# ESS-BoB.net
KiCad netlist of a schematic drawn in Altium Designer
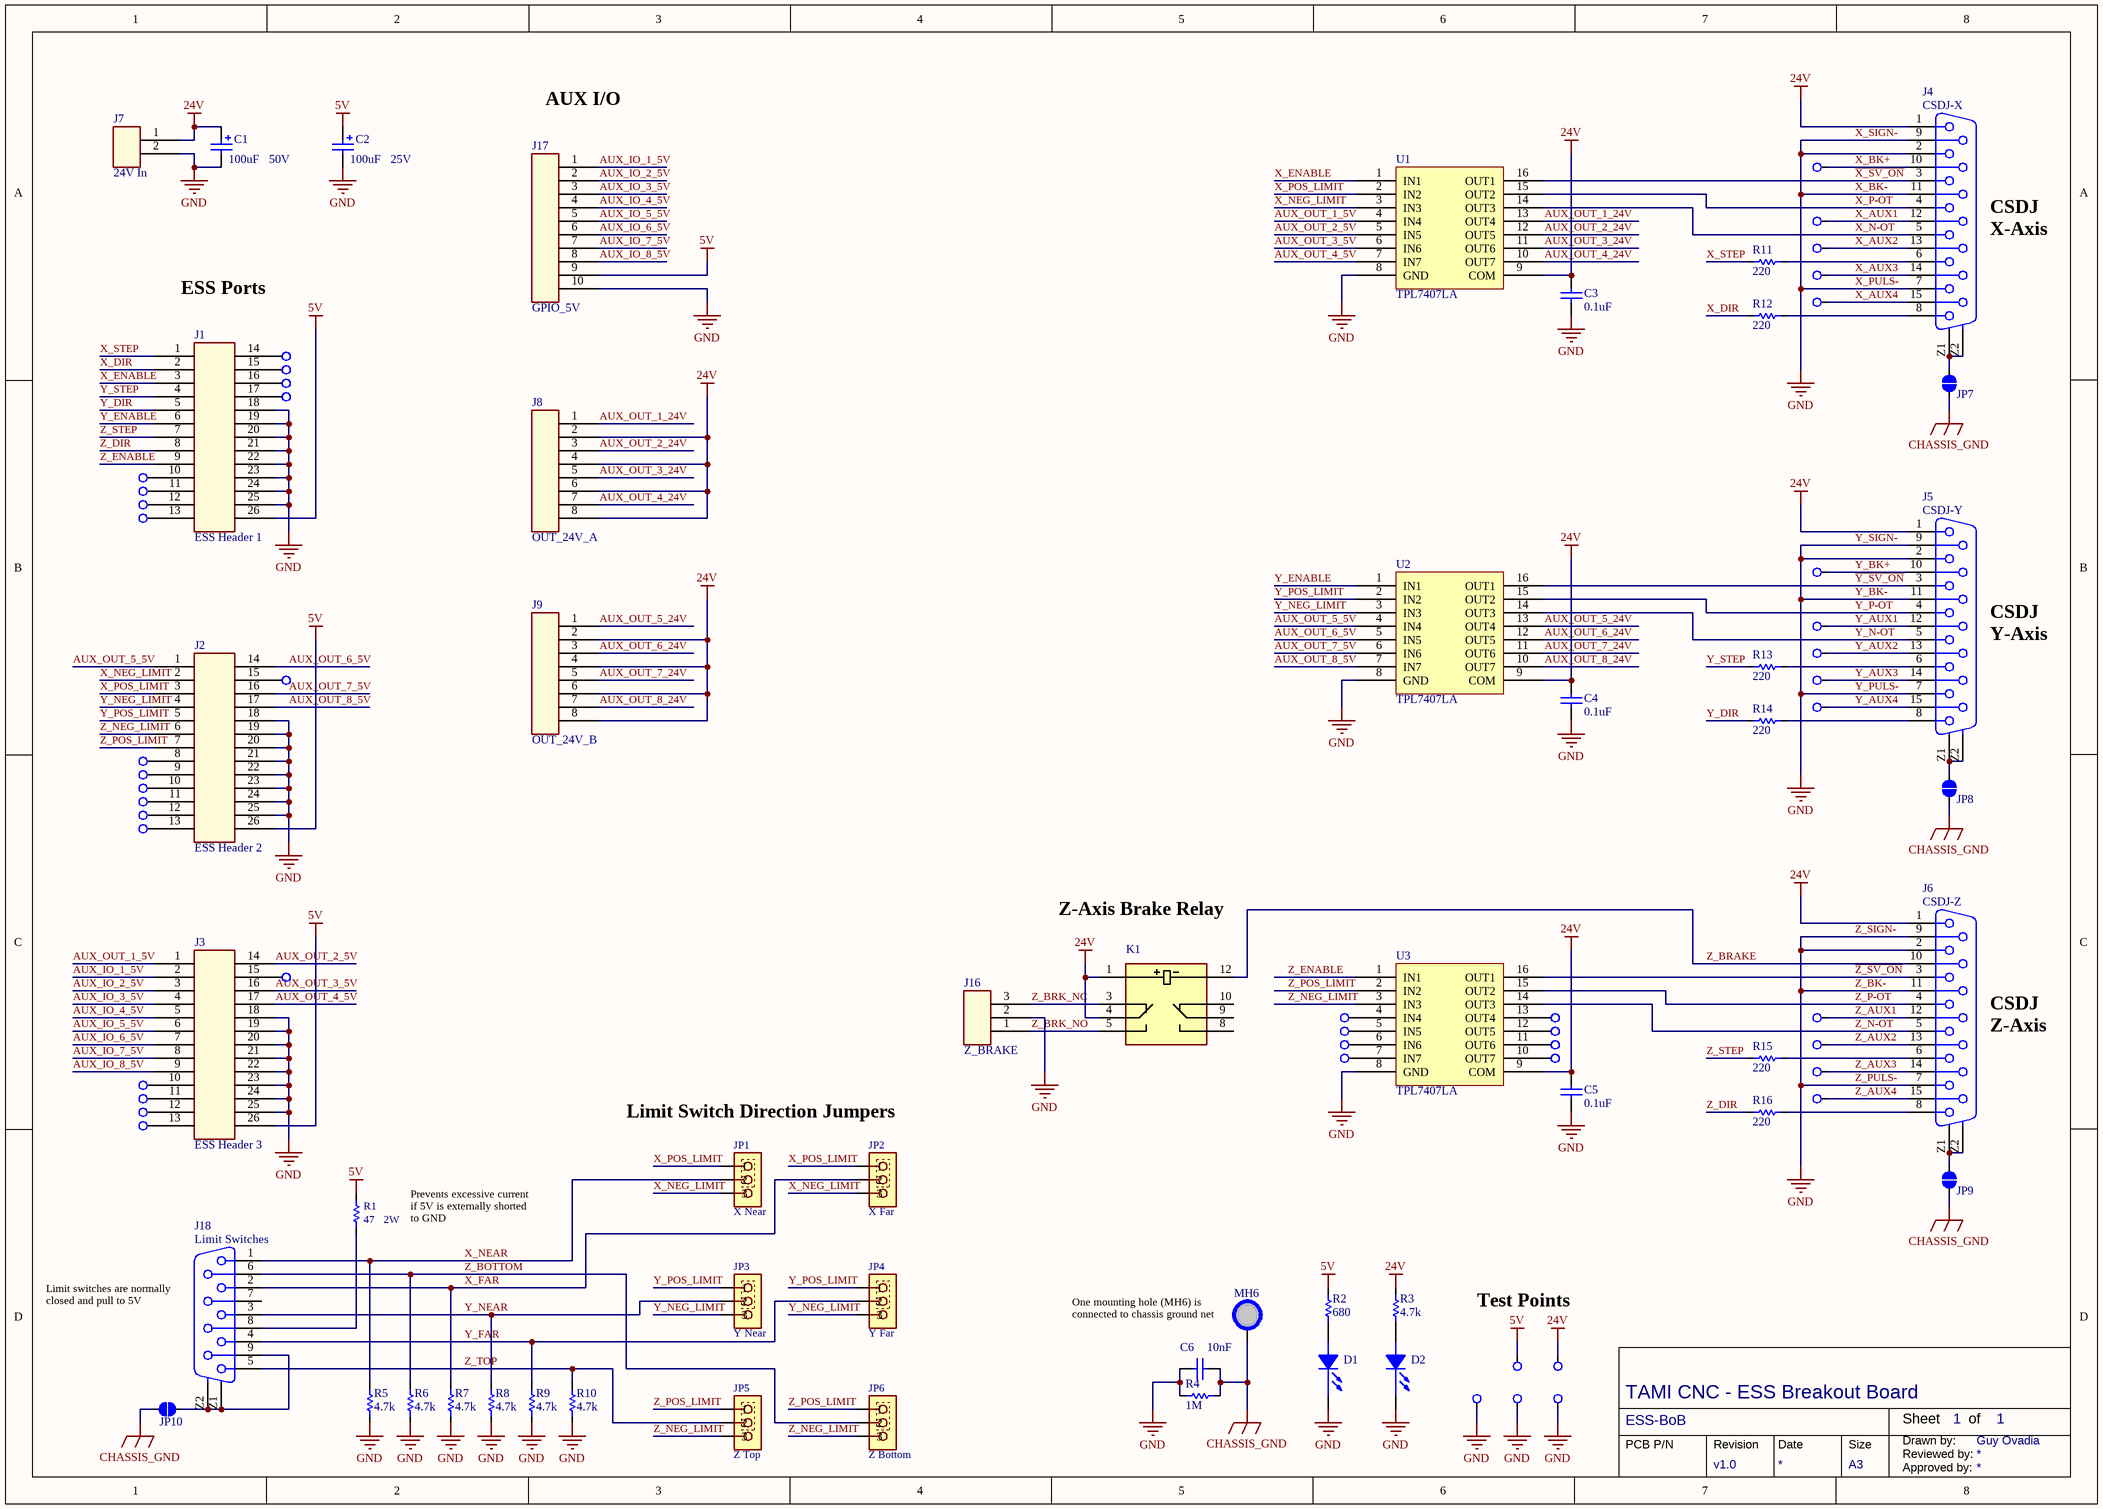
[diagram p0: ESS-BoB.SchDoc]

(export (version "E")
  (design (tool "Eeschema 10.0.6"))
  (components
    (comp (ref "C1")
      (value "100uF")
      (footprint "CAPPR3.5-8x12")
      (description "Polarized Capacitor")
      (fields
        (field (name "TOLERANCE") "TBD %")
        (field (name "VOLTAGE RATING") "50V")
        (field (name "Comment") "Cap Polarized")
      )
      (libsource (lib "my parts library") (part "Cap Polarized"))
    )
    (comp (ref "C2")
      (value "100uF")
      (footprint "CAPPR2-5x11")
      (description "Polarized Capacitor")
      (fields
        (field (name "TOLERANCE") "TBD %")
        (field (name "VOLTAGE RATING") "25V")
        (field (name "Comment") "Cap Polarized")
      )
      (libsource (lib "my parts library") (part "Cap Polarized"))
    )
    (comp (ref "C3")
      (value "0.1uF")
      (footprint "CAPC2012N")
      (description "Capacitor, non-polarized")
      (fields (field (name "TOLERANCE") "TBD %") (field (name "Comment") "Cap non-polarized"))
      (libsource (lib "my parts library") (part "Cap non-polarized"))
    )
    (comp (ref "C4")
      (value "0.1uF")
      (footprint "CAPC2012N")
      (description "Capacitor, non-polarized")
      (fields (field (name "TOLERANCE") "TBD %") (field (name "Comment") "Cap non-polarized"))
      (libsource (lib "my parts library") (part "Cap non-polarized"))
    )
    (comp (ref "C5")
      (value "0.1uF")
      (footprint "CAPC2012N")
      (description "Capacitor, non-polarized")
      (fields (field (name "TOLERANCE") "TBD %") (field (name "Comment") "Cap non-polarized"))
      (libsource (lib "my parts library") (part "Cap non-polarized"))
    )
    (comp (ref "C6")
      (value "10nF")
      (footprint "CAPC2012N")
      (description "Capacitor, non-polarized")
      (fields (field (name "TOLERANCE") "TBD %") (field (name "Comment") "Cap non-polarized"))
      (libsource (lib "my parts library") (part "Cap non-polarized"))
    )
    (comp (ref "D1") (value "5V") (footprint "LED-3MM-RED") (libsource (lib "my parts library") (part "LED")))
    (comp (ref "D2")
      (value "24V")
      (footprint "LED-3MM-RED")
      (libsource (lib "my parts library") (part "LED"))
    )
    (comp (ref "J1")
      (value "ESS Header 1")
      (footprint "Samtec ESQ-113-33-G-D")
      (libsource (lib "my parts library") (part "CON2x13 Alt. Numbering"))
    )
    (comp (ref "J2")
      (value "ESS Header 2")
      (footprint "Samtec ESQ-113-33-G-D")
      (libsource (lib "my parts library") (part "CON2x13 Alt. Numbering"))
    )
    (comp (ref "J3")
      (value "ESS Header 3")
      (footprint "Samtec ESQ-113-33-G-D")
      (libsource (lib "my parts library") (part "CON2x13 Alt. Numbering"))
    )
    (comp (ref "J4")
      (value "CSDJ-X")
      (footprint "D-SUB-15 FEMALE TH STRAIGHT")
      (description "WR-DSUB Female Angled PCB Connector")
      (libsource (lib "my parts library") (part "D-Sub-15 Wurth 618015231121"))
    )
    (comp (ref "J5")
      (value "CSDJ-Y")
      (footprint "D-SUB-15 FEMALE TH STRAIGHT")
      (description "WR-DSUB Female Angled PCB Connector")
      (libsource (lib "my parts library") (part "D-Sub-15 Wurth 618015231121"))
    )
    (comp (ref "J6")
      (value "CSDJ-Z")
      (footprint "D-SUB-15 FEMALE TH STRAIGHT")
      (description "WR-DSUB Female Angled PCB Connector")
      (libsource (lib "my parts library") (part "D-Sub-15 Wurth 618015231121"))
    )
    (comp (ref "J7")
      (value "24V In")
      (footprint "Modular Screw Terminals 5.08mm 2p RA TH")
      (libsource (lib "my parts library") (part "CON2"))
    )
    (comp (ref "J8")
      (value "OUT_24V_A")
      (footprint "Modular Screw Terminals 3.5mm 8p RA TH MOLEX")
      (libsource (lib "my parts library") (part "CON8"))
    )
    (comp (ref "J9")
      (value "OUT_24V_B")
      (footprint "Modular Screw Terminals 3.5mm 8p RA TH MOLEX")
      (libsource (lib "my parts library") (part "CON8"))
    )
    (comp (ref "J16")
      (value "Z_BRAKE")
      (footprint "Modular Screw Terminals 3.5mm 3p RA TH MOLEX")
      (libsource (lib "my parts library") (part "CON3"))
    )
    (comp (ref "J17")
      (value "GPIO_5V")
      (footprint "Modular Screw Terminals 3.5mm 10p RA TH MOLEX")
      (libsource (lib "my parts library") (part "CON10"))
    )
    (comp (ref "J18")
      (value "Limit Switches")
      (footprint "D-SUB-9 FEMALE TH RA")
      (description "WR-DSUB Female Angled PCB Connector")
      (libsource (lib "my parts library") (part "D-Sub-9 Wurth 618009231121"))
    )
    (comp (ref "JP1")
      (value "X Near")
      (footprint "Header 2.54mm 3p TH Vertical")
      (description "Jumper Header - SPDT")
      (libsource (lib "my parts library") (part "Jumper Header SPDT"))
    )
    (comp (ref "JP2")
      (value "X Far")
      (footprint "Header 2.54mm 3p TH Vertical")
      (description "Jumper Header - SPDT")
      (libsource (lib "my parts library") (part "Jumper Header SPDT"))
    )
    (comp (ref "JP3")
      (value "Y Near")
      (footprint "Header 2.54mm 3p TH Vertical")
      (description "Jumper Header - SPDT")
      (libsource (lib "my parts library") (part "Jumper Header SPDT"))
    )
    (comp (ref "JP4")
      (value "Y Far")
      (footprint "Header 2.54mm 3p TH Vertical")
      (description "Jumper Header - SPDT")
      (libsource (lib "my parts library") (part "Jumper Header SPDT"))
    )
    (comp (ref "JP5")
      (value "Z Top")
      (footprint "Header 2.54mm 3p TH Vertical")
      (description "Jumper Header - SPDT")
      (libsource (lib "my parts library") (part "Jumper Header SPDT"))
    )
    (comp (ref "JP6")
      (value "Z Bottom")
      (footprint "Header 2.54mm 3p TH Vertical")
      (description "Jumper Header - SPDT")
      (libsource (lib "my parts library") (part "Jumper Header SPDT"))
    )
    (comp (ref "JP7")
      (value "Solder Jumper NO")
      (footprint "SOLDER JUMPER NO 1.6mm")
      (libsource (lib "my parts library") (part "Solder Jumper NO"))
    )
    (comp (ref "JP8")
      (value "Solder Jumper NO")
      (footprint "SOLDER JUMPER NO 1.6mm")
      (libsource (lib "my parts library") (part "Solder Jumper NO"))
    )
    (comp (ref "JP9")
      (value "Solder Jumper NO")
      (footprint "SOLDER JUMPER NO 1.6mm")
      (libsource (lib "my parts library") (part "Solder Jumper NO"))
    )
    (comp (ref "JP10")
      (value "Solder Jumper NO")
      (footprint "SOLDER JUMPER NO 1.6mm")
      (libsource (lib "my parts library") (part "Solder Jumper NO"))
    )
    (comp (ref "K1")
      (value "V23079A1001B301 _1393788-3_")
      (footprint "TE_RELAY_V23079_TH")
      (description "V23079A1001B301")
      (fields (field (name "MF") "TE Connectivity") (field (name "MP") "1393788-3"))
      (libsource (lib "my parts library") (part "RELAY_TE_ V23079"))
    )
    (comp (ref "MH6")
      (value "Mounting Hole")
      (footprint "HOLE M4")
      (description "Mounting Hole with electrical connection")
      (libsource (lib "my parts library") (part "Mounting Hole"))
    )
    (comp (ref "R1")
      (value "47")
      (footprint "RESC6332N")
      (description "Resistor")
      (fields (field (name "POWER (WATTS)") "2W"))
      (libsource (lib "my parts library") (part "Resistor"))
    )
    (comp (ref "R2")
      (value "680")
      (footprint "RESC2012N")
      (description "Resistor")
      (fields (field (name "TOLERANCE") "TBD%"))
      (libsource (lib "my parts library") (part "Resistor"))
    )
    (comp (ref "R3")
      (value "4.7k")
      (footprint "RESC2012N")
      (description "Resistor")
      (fields (field (name "TOLERANCE") "TBD%"))
      (libsource (lib "my parts library") (part "Resistor"))
    )
    (comp (ref "R4")
      (value "1M")
      (footprint "RESC2012N")
      (description "Resistor")
      (fields (field (name "TOLERANCE") "TBD%"))
      (libsource (lib "my parts library") (part "Resistor"))
    )
    (comp (ref "R5")
      (value "4.7k")
      (footprint "RESC2012N")
      (description "Resistor")
      (libsource (lib "my parts library") (part "Resistor"))
    )
    (comp (ref "R6")
      (value "4.7k")
      (footprint "RESC2012N")
      (description "Resistor")
      (libsource (lib "my parts library") (part "Resistor"))
    )
    (comp (ref "R7")
      (value "4.7k")
      (footprint "RESC2012N")
      (description "Resistor")
      (libsource (lib "my parts library") (part "Resistor"))
    )
    (comp (ref "R8")
      (value "4.7k")
      (footprint "RESC2012N")
      (description "Resistor")
      (libsource (lib "my parts library") (part "Resistor"))
    )
    (comp (ref "R9")
      (value "4.7k")
      (footprint "RESC2012N")
      (description "Resistor")
      (libsource (lib "my parts library") (part "Resistor"))
    )
    (comp (ref "R10")
      (value "4.7k")
      (footprint "RESC2012N")
      (description "Resistor")
      (libsource (lib "my parts library") (part "Resistor"))
    )
    (comp (ref "R11")
      (value "220")
      (footprint "RESC2012N")
      (description "Resistor")
      (fields (field (name "TOLERANCE") "TBD%"))
      (libsource (lib "my parts library") (part "Resistor"))
    )
    (comp (ref "R12")
      (value "220")
      (footprint "RESC2012N")
      (description "Resistor")
      (fields (field (name "TOLERANCE") "TBD%"))
      (libsource (lib "my parts library") (part "Resistor"))
    )
    (comp (ref "R13")
      (value "220")
      (footprint "RESC2012N")
      (description "Resistor")
      (fields (field (name "TOLERANCE") "TBD%"))
      (libsource (lib "my parts library") (part "Resistor"))
    )
    (comp (ref "R14")
      (value "220")
      (footprint "RESC2012N")
      (description "Resistor")
      (fields (field (name "TOLERANCE") "TBD%"))
      (libsource (lib "my parts library") (part "Resistor"))
    )
    (comp (ref "R15")
      (value "220")
      (footprint "RESC2012N")
      (description "Resistor")
      (fields (field (name "TOLERANCE") "TBD%"))
      (libsource (lib "my parts library") (part "Resistor"))
    )
    (comp (ref "R16")
      (value "220")
      (footprint "RESC2012N")
      (description "Resistor")
      (fields (field (name "TOLERANCE") "TBD%"))
      (libsource (lib "my parts library") (part "Resistor"))
    )
    (comp (ref "TP1")
      (value "~")
      (footprint "TEST PAD TH")
      (libsource (lib "my parts library") (part "TEST_POINT"))
    )
    (comp (ref "TP2")
      (value "~")
      (footprint "TEST PAD TH")
      (libsource (lib "my parts library") (part "TEST_POINT"))
    )
    (comp (ref "TP3")
      (value "~")
      (footprint "TEST PAD TH")
      (libsource (lib "my parts library") (part "TEST_POINT"))
    )
    (comp (ref "TP4")
      (value "~")
      (footprint "TEST PAD TH")
      (libsource (lib "my parts library") (part "TEST_POINT"))
    )
    (comp (ref "TP5")
      (value "~")
      (footprint "TEST PAD TH")
      (libsource (lib "my parts library") (part "TEST_POINT"))
    )
    (comp (ref "TP6")
      (value "~")
      (footprint "TEST PAD TH")
      (libsource (lib "my parts library") (part "TEST_POINT"))
    )
    (comp (ref "TP7")
      (value "~")
      (footprint "TEST PAD TH")
      (libsource (lib "my parts library") (part "TEST_POINT"))
    )
    (comp (ref "TP8")
      (value "~")
      (footprint "TEST PAD TH")
      (libsource (lib "my parts library") (part "TEST_POINT"))
    )
    (comp (ref "TP9")
      (value "~")
      (footprint "TEST PAD TH")
      (libsource (lib "my parts library") (part "TEST_POINT"))
    )
    (comp (ref "TP10")
      (value "~")
      (footprint "TEST PAD TH")
      (libsource (lib "my parts library") (part "TEST_POINT"))
    )
    (comp (ref "TP11")
      (value "~")
      (footprint "TEST PAD TH")
      (libsource (lib "my parts library") (part "TEST_POINT"))
    )
    (comp (ref "TP12")
      (value "~")
      (footprint "TEST PAD TH")
      (libsource (lib "my parts library") (part "TEST_POINT"))
    )
    (comp (ref "TP13")
      (value "~")
      (footprint "TEST PAD TH")
      (libsource (lib "my parts library") (part "TEST_POINT"))
    )
    (comp (ref "TP14")
      (value "~")
      (footprint "TEST PAD TH")
      (libsource (lib "my parts library") (part "TEST_POINT"))
    )
    (comp (ref "TP15")
      (value "~")
      (footprint "TEST PAD TH")
      (libsource (lib "my parts library") (part "TEST_POINT"))
    )
    (comp (ref "TP16")
      (value "~")
      (footprint "TEST PAD TH")
      (libsource (lib "my parts library") (part "TEST_POINT"))
    )
    (comp (ref "TP17")
      (value "~")
      (footprint "TEST PAD TH")
      (libsource (lib "my parts library") (part "TEST_POINT"))
    )
    (comp (ref "TP18")
      (value "~")
      (footprint "TEST PAD TH")
      (libsource (lib "my parts library") (part "TEST_POINT"))
    )
    (comp (ref "TP19")
      (value "~")
      (footprint "TEST PAD TH")
      (libsource (lib "my parts library") (part "TEST_POINT"))
    )
    (comp (ref "TP20")
      (value "~")
      (footprint "TEST PAD TH")
      (libsource (lib "my parts library") (part "TEST_POINT"))
    )
    (comp (ref "TP21")
      (value "~")
      (footprint "TEST PAD TH")
      (libsource (lib "my parts library") (part "TEST_POINT"))
    )
    (comp (ref "TP22")
      (value "~")
      (footprint "TEST PAD TH")
      (libsource (lib "my parts library") (part "TEST_POINT"))
    )
    (comp (ref "TP23")
      (value "~")
      (footprint "TEST PAD TH")
      (libsource (lib "my parts library") (part "TEST_POINT"))
    )
    (comp (ref "TP24")
      (value "~")
      (footprint "TEST PAD TH")
      (libsource (lib "my parts library") (part "TEST_POINT"))
    )
    (comp (ref "TP25")
      (value "~")
      (footprint "TEST PAD TH")
      (libsource (lib "my parts library") (part "TEST_POINT"))
    )
    (comp (ref "TP26")
      (value "~")
      (footprint "TEST PAD TH")
      (libsource (lib "my parts library") (part "TEST_POINT"))
    )
    (comp (ref "TP27")
      (value "~")
      (footprint "TEST PAD TH")
      (libsource (lib "my parts library") (part "TEST_POINT"))
    )
    (comp (ref "TP28")
      (value "~")
      (footprint "TEST PAD TH")
      (libsource (lib "my parts library") (part "TEST_POINT"))
    )
    (comp (ref "TP29")
      (value "~")
      (footprint "TEST PAD TH")
      (libsource (lib "my parts library") (part "TEST_POINT"))
    )
    (comp (ref "TP30")
      (value "~")
      (footprint "TEST PAD TH")
      (libsource (lib "my parts library") (part "TEST_POINT"))
    )
    (comp (ref "TP31")
      (value "~")
      (footprint "TEST PAD TH")
      (libsource (lib "my parts library") (part "TEST_POINT"))
    )
    (comp (ref "TP32")
      (value "~")
      (footprint "TEST PAD TH")
      (libsource (lib "my parts library") (part "TEST_POINT"))
    )
    (comp (ref "TP33")
      (value "~")
      (footprint "TEST PAD TH")
      (libsource (lib "my parts library") (part "TEST_POINT"))
    )
    (comp (ref "TP34")
      (value "~")
      (footprint "TEST PAD TH")
      (libsource (lib "my parts library") (part "TEST_POINT"))
    )
    (comp (ref "TP35")
      (value "~")
      (footprint "TEST PAD TH")
      (libsource (lib "my parts library") (part "TEST_POINT"))
    )
    (comp (ref "TP36")
      (value "~")
      (footprint "TEST PAD TH")
      (libsource (lib "my parts library") (part "TEST_POINT"))
    )
    (comp (ref "TP37")
      (value "~")
      (footprint "TEST PAD TH")
      (libsource (lib "my parts library") (part "TEST_POINT"))
    )
    (comp (ref "TP38")
      (value "~")
      (footprint "TEST PAD TH")
      (libsource (lib "my parts library") (part "TEST_POINT"))
    )
    (comp (ref "TP39")
      (value "~")
      (footprint "TEST PAD TH")
      (libsource (lib "my parts library") (part "TEST_POINT"))
    )
    (comp (ref "TP40")
      (value "~")
      (footprint "TEST PAD TH")
      (libsource (lib "my parts library") (part "TEST_POINT"))
    )
    (comp (ref "TP41")
      (value "~")
      (footprint "TEST PAD TH")
      (libsource (lib "my parts library") (part "TEST_POINT"))
    )
    (comp (ref "TP42")
      (value "~")
      (footprint "TEST PAD TH")
      (libsource (lib "my parts library") (part "TEST_POINT"))
    )
    (comp (ref "TP43")
      (value "5V")
      (footprint "TP_LOOP_1MM - WHITE")
      (libsource (lib "my parts library") (part "TEST_POINT"))
    )
    (comp (ref "TP44")
      (value "24V")
      (footprint "TP_LOOP_1MM - WHITE")
      (libsource (lib "my parts library") (part "TEST_POINT"))
    )
    (comp (ref "TP45")
      (value "GND")
      (footprint "TP_LOOP_1MM - BLACK")
      (libsource (lib "my parts library") (part "TEST_POINT"))
    )
    (comp (ref "TP46")
      (value "GND")
      (footprint "TP_LOOP_1MM - BLACK")
      (libsource (lib "my parts library") (part "TEST_POINT"))
    )
    (comp (ref "TP47")
      (value "GND")
      (footprint "TP_LOOP_1MM - BLACK")
      (libsource (lib "my parts library") (part "TEST_POINT"))
    )
    (comp (ref "U1")
      (value "TPL7407LA")
      (footprint "TI D016_M (SOIC16)")
      (description "Solenoid Driver")
      (libsource (lib "my parts library") (part "TPL7407L"))
    )
    (comp (ref "U2")
      (value "TPL7407LA")
      (footprint "TI D016_M (SOIC16)")
      (description "Solenoid Driver")
      (libsource (lib "my parts library") (part "TPL7407L"))
    )
    (comp (ref "U3")
      (value "TPL7407LA")
      (footprint "TI D016_M (SOIC16)")
      (description "Solenoid Driver")
      (libsource (lib "my parts library") (part "TPL7407L"))
    )
  )
  (nets
    (net (code "1") (name "/AUX_IO_1_5V") (class "Default")
      (node (ref "J17") (pin "1") (pinfunction "1_1") (pintype "passive"))
      (node (ref "J3") (pin "2") (pinfunction "2_2") (pintype "passive"))
    )
    (net (code "2") (name "/AUX_IO_2_5V") (class "Default")
      (node (ref "J17") (pin "2") (pinfunction "2_2") (pintype "passive"))
      (node (ref "J3") (pin "3") (pinfunction "3_3") (pintype "passive"))
    )
    (net (code "3") (name "/AUX_IO_3_5V") (class "Default")
      (node (ref "J17") (pin "3") (pinfunction "3_3") (pintype "passive"))
      (node (ref "J3") (pin "4") (pinfunction "4_4") (pintype "passive"))
    )
    (net (code "4") (name "/AUX_IO_4_5V") (class "Default")
      (node (ref "J17") (pin "4") (pinfunction "4_4") (pintype "passive"))
      (node (ref "J3") (pin "5") (pinfunction "5_5") (pintype "passive"))
    )
    (net (code "5") (name "/AUX_IO_5_5V") (class "Default")
      (node (ref "J17") (pin "5") (pinfunction "5_5") (pintype "passive"))
      (node (ref "J3") (pin "6") (pinfunction "6_6") (pintype "passive"))
    )
    (net (code "6") (name "/AUX_IO_6_5V") (class "Default")
      (node (ref "J17") (pin "6") (pinfunction "6_6") (pintype "passive"))
      (node (ref "J3") (pin "7") (pinfunction "7_7") (pintype "passive"))
    )
    (net (code "7") (name "/AUX_IO_7_5V") (class "Default")
      (node (ref "J17") (pin "7") (pinfunction "7_7") (pintype "passive"))
      (node (ref "J3") (pin "8") (pinfunction "8_8") (pintype "passive"))
    )
    (net (code "8") (name "/AUX_IO_8_5V") (class "Default")
      (node (ref "J17") (pin "8") (pinfunction "8_8") (pintype "passive"))
      (node (ref "J3") (pin "9") (pinfunction "9_9") (pintype "passive"))
    )
    (net (code "9") (name "/AUX_OUT_1_5V") (class "Default")
      (node (ref "J3") (pin "1") (pinfunction "1_1") (pintype "passive"))
      (node (ref "U1") (pin "4") (pinfunction "IN4_4") (pintype "passive"))
    )
    (net (code "10") (name "/AUX_OUT_1_24V") (class "Default")
      (node (ref "J8") (pin "1") (pinfunction "1_1") (pintype "passive"))
      (node (ref "U1") (pin "13") (pinfunction "OUT4_13") (pintype "passive"))
    )
    (net (code "11") (name "/AUX_OUT_2_5V") (class "Default")
      (node (ref "J3") (pin "14") (pinfunction "14_14") (pintype "passive"))
      (node (ref "U1") (pin "5") (pinfunction "IN5_5") (pintype "passive"))
    )
    (net (code "12") (name "/AUX_OUT_2_24V") (class "Default")
      (node (ref "J8") (pin "3") (pinfunction "3_3") (pintype "passive"))
      (node (ref "U1") (pin "12") (pinfunction "OUT5_12") (pintype "passive"))
    )
    (net (code "13") (name "/AUX_OUT_3_5V") (class "Default")
      (node (ref "J3") (pin "16") (pinfunction "16_16") (pintype "passive"))
      (node (ref "U1") (pin "6") (pinfunction "IN6_6") (pintype "passive"))
    )
    (net (code "14") (name "/AUX_OUT_3_24V") (class "Default")
      (node (ref "J8") (pin "5") (pinfunction "5_5") (pintype "passive"))
      (node (ref "U1") (pin "11") (pinfunction "OUT6_11") (pintype "passive"))
    )
    (net (code "15") (name "/AUX_OUT_4_5V") (class "Default")
      (node (ref "J3") (pin "17") (pinfunction "17_17") (pintype "passive"))
      (node (ref "U1") (pin "7") (pinfunction "IN7_7") (pintype "passive"))
    )
    (net (code "16") (name "/AUX_OUT_4_24V") (class "Default")
      (node (ref "J8") (pin "7") (pinfunction "7_7") (pintype "passive"))
      (node (ref "U1") (pin "10") (pinfunction "OUT7_10") (pintype "passive"))
    )
    (net (code "17") (name "/AUX_OUT_5_5V") (class "Default")
      (node (ref "J2") (pin "1") (pinfunction "1_1") (pintype "passive"))
      (node (ref "U2") (pin "4") (pinfunction "IN4_4") (pintype "passive"))
    )
    (net (code "18") (name "/AUX_OUT_5_24V") (class "Default")
      (node (ref "J9") (pin "1") (pinfunction "1_1") (pintype "passive"))
      (node (ref "U2") (pin "13") (pinfunction "OUT4_13") (pintype "passive"))
    )
    (net (code "19") (name "/AUX_OUT_6_5V") (class "Default")
      (node (ref "J2") (pin "14") (pinfunction "14_14") (pintype "passive"))
      (node (ref "U2") (pin "5") (pinfunction "IN5_5") (pintype "passive"))
    )
    (net (code "20") (name "/AUX_OUT_6_24V") (class "Default")
      (node (ref "J9") (pin "3") (pinfunction "3_3") (pintype "passive"))
      (node (ref "U2") (pin "12") (pinfunction "OUT5_12") (pintype "passive"))
    )
    (net (code "21") (name "/AUX_OUT_7_5V") (class "Default")
      (node (ref "J2") (pin "16") (pinfunction "16_16") (pintype "passive"))
      (node (ref "U2") (pin "6") (pinfunction "IN6_6") (pintype "passive"))
    )
    (net (code "22") (name "/AUX_OUT_7_24V") (class "Default")
      (node (ref "J9") (pin "5") (pinfunction "5_5") (pintype "passive"))
      (node (ref "U2") (pin "11") (pinfunction "OUT6_11") (pintype "passive"))
    )
    (net (code "23") (name "/AUX_OUT_8_5V") (class "Default")
      (node (ref "J2") (pin "17") (pinfunction "17_17") (pintype "passive"))
      (node (ref "U2") (pin "7") (pinfunction "IN7_7") (pintype "passive"))
    )
    (net (code "24") (name "/AUX_OUT_8_24V") (class "Default")
      (node (ref "J9") (pin "7") (pinfunction "7_7") (pintype "passive"))
      (node (ref "U2") (pin "10") (pinfunction "OUT7_10") (pintype "passive"))
    )
    (net (code "25") (name "/X_AUX1") (class "Default")
      (node (ref "J4") (pin "12") (pinfunction "12_12") (pintype "passive"))
      (node (ref "TP2") (pin "1") (pinfunction "TP_1") (pintype "passive"))
    )
    (net (code "26") (name "/X_AUX2") (class "Default")
      (node (ref "J4") (pin "13") (pinfunction "13_13") (pintype "passive"))
      (node (ref "TP3") (pin "1") (pinfunction "TP_1") (pintype "passive"))
    )
    (net (code "27") (name "/X_AUX3") (class "Default")
      (node (ref "J4") (pin "14") (pinfunction "14_14") (pintype "passive"))
      (node (ref "TP4") (pin "1") (pinfunction "TP_1") (pintype "passive"))
    )
    (net (code "28") (name "/X_AUX4") (class "Default")
      (node (ref "J4") (pin "15") (pinfunction "15_15") (pintype "passive"))
      (node (ref "TP5") (pin "1") (pinfunction "TP_1") (pintype "passive"))
    )
    (net (code "29") (name "/X_BK+") (class "Default")
      (node (ref "J4") (pin "10") (pinfunction "10_10") (pintype "passive"))
      (node (ref "TP1") (pin "1") (pinfunction "TP_1") (pintype "passive"))
    )
    (net (code "30") (name "/X_DIR") (class "Default")
      (node (ref "J1") (pin "2") (pinfunction "2_2") (pintype "passive"))
      (node (ref "R12") (pin "1") (pinfunction "1_1") (pintype "passive"))
    )
    (net (code "31") (name "/X_ENABLE") (class "Default")
      (node (ref "J1") (pin "3") (pinfunction "3_3") (pintype "passive"))
      (node (ref "U1") (pin "1") (pinfunction "IN1_1") (pintype "passive"))
    )
    (net (code "32") (name "/X_FAR") (class "Default")
      (node (ref "J18") (pin "2") (pinfunction "2_2") (pintype "passive"))
      (node (ref "JP2") (pin "2") (pinfunction "2_2") (pintype "passive"))
      (node (ref "R7") (pin "2") (pinfunction "2_2") (pintype "passive"))
    )
    (net (code "33") (name "/X_N-OT") (class "Default")
      (node (ref "J4") (pin "5") (pinfunction "5_5") (pintype "passive"))
      (node (ref "U1") (pin "14") (pinfunction "OUT3_14") (pintype "passive"))
    )
    (net (code "34") (name "/X_NEAR") (class "Default")
      (node (ref "J18") (pin "1") (pinfunction "1_1") (pintype "passive"))
      (node (ref "JP1") (pin "2") (pinfunction "2_2") (pintype "passive"))
      (node (ref "R5") (pin "2") (pinfunction "2_2") (pintype "passive"))
    )
    (net (code "35") (name "/X_NEG_LIMIT") (class "Default")
      (node (ref "J2") (pin "2") (pinfunction "2_2") (pintype "passive"))
      (node (ref "JP1") (pin "3") (pinfunction "3_3") (pintype "passive"))
      (node (ref "JP2") (pin "3") (pinfunction "3_3") (pintype "passive"))
      (node (ref "U1") (pin "3") (pinfunction "IN3_3") (pintype "passive"))
    )
    (net (code "36") (name "/X_P-OT") (class "Default")
      (node (ref "J4") (pin "4") (pinfunction "4_4") (pintype "passive"))
      (node (ref "U1") (pin "15") (pinfunction "OUT2_15") (pintype "passive"))
    )
    (net (code "37") (name "/X_POS_LIMIT") (class "Default")
      (node (ref "J2") (pin "3") (pinfunction "3_3") (pintype "passive"))
      (node (ref "JP1") (pin "1") (pinfunction "1_1") (pintype "passive"))
      (node (ref "JP2") (pin "1") (pinfunction "1_1") (pintype "passive"))
      (node (ref "U1") (pin "2") (pinfunction "IN2_2") (pintype "passive"))
    )
    (net (code "38") (name "/X_STEP") (class "Default")
      (node (ref "J1") (pin "1") (pinfunction "1_1") (pintype "passive"))
      (node (ref "R11") (pin "1") (pinfunction "1_1") (pintype "passive"))
    )
    (net (code "39") (name "/X_SV_ON") (class "Default")
      (node (ref "J4") (pin "3") (pinfunction "3_3") (pintype "passive"))
      (node (ref "U1") (pin "16") (pinfunction "OUT1_16") (pintype "passive"))
    )
    (net (code "40") (name "/Y_AUX1") (class "Default")
      (node (ref "J5") (pin "12") (pinfunction "12_12") (pintype "passive"))
      (node (ref "TP15") (pin "1") (pinfunction "TP_1") (pintype "passive"))
    )
    (net (code "41") (name "/Y_AUX2") (class "Default")
      (node (ref "J5") (pin "13") (pinfunction "13_13") (pintype "passive"))
      (node (ref "TP16") (pin "1") (pinfunction "TP_1") (pintype "passive"))
    )
    (net (code "42") (name "/Y_AUX3") (class "Default")
      (node (ref "J5") (pin "14") (pinfunction "14_14") (pintype "passive"))
      (node (ref "TP18") (pin "1") (pinfunction "TP_1") (pintype "passive"))
    )
    (net (code "43") (name "/Y_AUX4") (class "Default")
      (node (ref "J5") (pin "15") (pinfunction "15_15") (pintype "passive"))
      (node (ref "TP19") (pin "1") (pinfunction "TP_1") (pintype "passive"))
    )
    (net (code "44") (name "/Y_BK+") (class "Default")
      (node (ref "J5") (pin "10") (pinfunction "10_10") (pintype "passive"))
      (node (ref "TP14") (pin "1") (pinfunction "TP_1") (pintype "passive"))
    )
    (net (code "45") (name "/Y_DIR") (class "Default")
      (node (ref "J1") (pin "5") (pinfunction "5_5") (pintype "passive"))
      (node (ref "R14") (pin "1") (pinfunction "1_1") (pintype "passive"))
    )
    (net (code "46") (name "/Y_ENABLE") (class "Default")
      (node (ref "J1") (pin "6") (pinfunction "6_6") (pintype "passive"))
      (node (ref "U2") (pin "1") (pinfunction "IN1_1") (pintype "passive"))
    )
    (net (code "47") (name "/Y_FAR") (class "Default")
      (node (ref "J18") (pin "4") (pinfunction "4_4") (pintype "passive"))
      (node (ref "JP4") (pin "2") (pinfunction "2_2") (pintype "passive"))
      (node (ref "R9") (pin "2") (pinfunction "2_2") (pintype "passive"))
    )
    (net (code "48") (name "/Y_N-OT") (class "Default")
      (node (ref "J5") (pin "5") (pinfunction "5_5") (pintype "passive"))
      (node (ref "U2") (pin "14") (pinfunction "OUT3_14") (pintype "passive"))
    )
    (net (code "49") (name "/Y_NEAR") (class "Default")
      (node (ref "J18") (pin "3") (pinfunction "3_3") (pintype "passive"))
      (node (ref "JP3") (pin "2") (pinfunction "2_2") (pintype "passive"))
      (node (ref "R8") (pin "2") (pinfunction "2_2") (pintype "passive"))
    )
    (net (code "50") (name "/Y_NEG_LIMIT") (class "Default")
      (node (ref "J2") (pin "4") (pinfunction "4_4") (pintype "passive"))
      (node (ref "JP3") (pin "3") (pinfunction "3_3") (pintype "passive"))
      (node (ref "JP4") (pin "3") (pinfunction "3_3") (pintype "passive"))
      (node (ref "U2") (pin "3") (pinfunction "IN3_3") (pintype "passive"))
    )
    (net (code "51") (name "/Y_P-OT") (class "Default")
      (node (ref "J5") (pin "4") (pinfunction "4_4") (pintype "passive"))
      (node (ref "U2") (pin "15") (pinfunction "OUT2_15") (pintype "passive"))
    )
    (net (code "52") (name "/Y_POS_LIMIT") (class "Default")
      (node (ref "J2") (pin "5") (pinfunction "5_5") (pintype "passive"))
      (node (ref "JP3") (pin "1") (pinfunction "1_1") (pintype "passive"))
      (node (ref "JP4") (pin "1") (pinfunction "1_1") (pintype "passive"))
      (node (ref "U2") (pin "2") (pinfunction "IN2_2") (pintype "passive"))
    )
    (net (code "53") (name "/Y_STEP") (class "Default")
      (node (ref "J1") (pin "4") (pinfunction "4_4") (pintype "passive"))
      (node (ref "R13") (pin "1") (pinfunction "1_1") (pintype "passive"))
    )
    (net (code "54") (name "/Y_SV_ON") (class "Default")
      (node (ref "J5") (pin "3") (pinfunction "3_3") (pintype "passive"))
      (node (ref "U2") (pin "16") (pinfunction "OUT1_16") (pintype "passive"))
    )
    (net (code "55") (name "/Z_AUX1") (class "Default")
      (node (ref "J6") (pin "12") (pinfunction "12_12") (pintype "passive"))
      (node (ref "TP29") (pin "1") (pinfunction "TP_1") (pintype "passive"))
    )
    (net (code "56") (name "/Z_AUX2") (class "Default")
      (node (ref "J6") (pin "13") (pinfunction "13_13") (pintype "passive"))
      (node (ref "TP34") (pin "1") (pinfunction "TP_1") (pintype "passive"))
    )
    (net (code "57") (name "/Z_AUX3") (class "Default")
      (node (ref "J6") (pin "14") (pinfunction "14_14") (pintype "passive"))
      (node (ref "TP37") (pin "1") (pinfunction "TP_1") (pintype "passive"))
    )
    (net (code "58") (name "/Z_AUX4") (class "Default")
      (node (ref "J6") (pin "15") (pinfunction "15_15") (pintype "passive"))
      (node (ref "TP40") (pin "1") (pinfunction "TP_1") (pintype "passive"))
    )
    (net (code "59") (name "/Z_BOTTOM") (class "Default")
      (node (ref "J18") (pin "6") (pinfunction "6_6") (pintype "passive"))
      (node (ref "JP6") (pin "2") (pinfunction "2_2") (pintype "passive"))
      (node (ref "R6") (pin "2") (pinfunction "2_2") (pintype "passive"))
    )
    (net (code "60") (name "/Z_BRAKE") (class "Default")
      (node (ref "J6") (pin "10") (pinfunction "10_10") (pintype "passive"))
      (node (ref "K1") (pin "12") (pinfunction "12_12") (pintype "passive"))
    )
    (net (code "61") (name "/Z_BRK_NC") (class "Default")
      (node (ref "J16") (pin "3") (pinfunction "3_3") (pintype "passive"))
      (node (ref "K1") (pin "3") (pinfunction "3_3") (pintype "passive"))
    )
    (net (code "62") (name "/Z_BRK_NO") (class "Default")
      (node (ref "J16") (pin "1") (pinfunction "1_1") (pintype "passive"))
      (node (ref "K1") (pin "5") (pinfunction "5_5") (pintype "passive"))
    )
    (net (code "63") (name "/Z_DIR") (class "Default")
      (node (ref "J1") (pin "8") (pinfunction "8_8") (pintype "passive"))
      (node (ref "R16") (pin "1") (pinfunction "1_1") (pintype "passive"))
    )
    (net (code "64") (name "/Z_ENABLE") (class "Default")
      (node (ref "J1") (pin "9") (pinfunction "9_9") (pintype "passive"))
      (node (ref "U3") (pin "1") (pinfunction "IN1_1") (pintype "passive"))
    )
    (net (code "65") (name "/Z_N-OT") (class "Default")
      (node (ref "J6") (pin "5") (pinfunction "5_5") (pintype "passive"))
      (node (ref "U3") (pin "14") (pinfunction "OUT3_14") (pintype "passive"))
    )
    (net (code "66") (name "/Z_NEG_LIMIT") (class "Default")
      (node (ref "J2") (pin "6") (pinfunction "6_6") (pintype "passive"))
      (node (ref "JP5") (pin "3") (pinfunction "3_3") (pintype "passive"))
      (node (ref "JP6") (pin "3") (pinfunction "3_3") (pintype "passive"))
      (node (ref "U3") (pin "3") (pinfunction "IN3_3") (pintype "passive"))
    )
    (net (code "67") (name "/Z_P-OT") (class "Default")
      (node (ref "J6") (pin "4") (pinfunction "4_4") (pintype "passive"))
      (node (ref "U3") (pin "15") (pinfunction "OUT2_15") (pintype "passive"))
    )
    (net (code "68") (name "/Z_POS_LIMIT") (class "Default")
      (node (ref "J2") (pin "7") (pinfunction "7_7") (pintype "passive"))
      (node (ref "JP5") (pin "1") (pinfunction "1_1") (pintype "passive"))
      (node (ref "JP6") (pin "1") (pinfunction "1_1") (pintype "passive"))
      (node (ref "U3") (pin "2") (pinfunction "IN2_2") (pintype "passive"))
    )
    (net (code "69") (name "/Z_STEP") (class "Default")
      (node (ref "J1") (pin "7") (pinfunction "7_7") (pintype "passive"))
      (node (ref "R15") (pin "1") (pinfunction "1_1") (pintype "passive"))
    )
    (net (code "70") (name "/Z_SV_ON") (class "Default")
      (node (ref "J6") (pin "3") (pinfunction "3_3") (pintype "passive"))
      (node (ref "U3") (pin "16") (pinfunction "OUT1_16") (pintype "passive"))
    )
    (net (code "71") (name "/Z_TOP") (class "Default")
      (node (ref "J18") (pin "5") (pinfunction "5_5") (pintype "passive"))
      (node (ref "JP5") (pin "2") (pinfunction "2_2") (pintype "passive"))
      (node (ref "R10") (pin "2") (pinfunction "2_2") (pintype "passive"))
    )
    (net (code "72") (name "5V") (class "Default")
      (node (ref "C2") (pin "1") (pinfunction "1_1") (pintype "passive"))
      (node (ref "J1") (pin "26") (pinfunction "26_26") (pintype "passive"))
      (node (ref "J17") (pin "9") (pinfunction "9_9") (pintype "passive"))
      (node (ref "J2") (pin "26") (pinfunction "26_26") (pintype "passive"))
      (node (ref "J3") (pin "26") (pinfunction "26_26") (pintype "passive"))
      (node (ref "R1") (pin "2") (pinfunction "2_2") (pintype "passive"))
      (node (ref "R2") (pin "2") (pinfunction "2_2") (pintype "passive"))
      (node (ref "TP43") (pin "1") (pinfunction "TP_1") (pintype "passive"))
    )
    (net (code "73") (name "24V") (class "Default")
      (node (ref "C1") (pin "1") (pinfunction "1_1") (pintype "passive"))
      (node (ref "C3") (pin "2") (pinfunction "2_2") (pintype "passive"))
      (node (ref "C4") (pin "2") (pinfunction "2_2") (pintype "passive"))
      (node (ref "C5") (pin "2") (pinfunction "2_2") (pintype "passive"))
      (node (ref "J4") (pin "1") (pinfunction "1_1") (pintype "passive"))
      (node (ref "J5") (pin "1") (pinfunction "1_1") (pintype "passive"))
      (node (ref "J6") (pin "1") (pinfunction "1_1") (pintype "passive"))
      (node (ref "J7") (pin "1") (pinfunction "1_1") (pintype "passive"))
      (node (ref "J8") (pin "2") (pinfunction "2_2") (pintype "passive"))
      (node (ref "J8") (pin "4") (pinfunction "4_4") (pintype "passive"))
      (node (ref "J8") (pin "6") (pinfunction "6_6") (pintype "passive"))
      (node (ref "J8") (pin "8") (pinfunction "8_8") (pintype "passive"))
      (node (ref "J9") (pin "2") (pinfunction "2_2") (pintype "passive"))
      (node (ref "J9") (pin "4") (pinfunction "4_4") (pintype "passive"))
      (node (ref "J9") (pin "6") (pinfunction "6_6") (pintype "passive"))
      (node (ref "J9") (pin "8") (pinfunction "8_8") (pintype "passive"))
      (node (ref "K1") (pin "1") (pinfunction "1_1") (pintype "passive"))
      (node (ref "K1") (pin "4") (pinfunction "4_4") (pintype "passive"))
      (node (ref "R3") (pin "2") (pinfunction "2_2") (pintype "passive"))
      (node (ref "TP44") (pin "1") (pinfunction "TP_1") (pintype "passive"))
      (node (ref "U1") (pin "9") (pinfunction "COM_9") (pintype "passive"))
      (node (ref "U2") (pin "9") (pinfunction "COM_9") (pintype "passive"))
      (node (ref "U3") (pin "9") (pinfunction "COM_9") (pintype "passive"))
    )
    (net (code "74") (name "CHASSIS_GND") (class "Default")
      (node (ref "C6") (pin "1") (pinfunction "1_1") (pintype "passive"))
      (node (ref "JP10") (pin "2") (pinfunction "2_2") (pintype "passive"))
      (node (ref "JP7") (pin "1") (pinfunction "1_1") (pintype "passive"))
      (node (ref "JP8") (pin "1") (pinfunction "1_1") (pintype "passive"))
      (node (ref "JP9") (pin "1") (pinfunction "1_1") (pintype "passive"))
      (node (ref "MH6") (pin "1") (pinfunction "MH_1") (pintype "passive"))
      (node (ref "R4") (pin "2") (pinfunction "2_2") (pintype "passive"))
    )
    (net (code "75") (name "GND") (class "Default")
      (node (ref "C1") (pin "2") (pinfunction "2_2") (pintype "passive"))
      (node (ref "C2") (pin "2") (pinfunction "2_2") (pintype "passive"))
      (node (ref "C3") (pin "1") (pinfunction "1_1") (pintype "passive"))
      (node (ref "C4") (pin "1") (pinfunction "1_1") (pintype "passive"))
      (node (ref "C5") (pin "1") (pinfunction "1_1") (pintype "passive"))
      (node (ref "C6") (pin "2") (pinfunction "2_2") (pintype "passive"))
      (node (ref "D1") (pin "K") (pinfunction "CATHODE_K") (pintype "passive"))
      (node (ref "D2") (pin "K") (pinfunction "CATHODE_K") (pintype "passive"))
      (node (ref "J1") (pin "18") (pinfunction "18_18") (pintype "passive"))
      (node (ref "J1") (pin "19") (pinfunction "19_19") (pintype "passive"))
      (node (ref "J1") (pin "20") (pinfunction "20_20") (pintype "passive"))
      (node (ref "J1") (pin "21") (pinfunction "21_21") (pintype "passive"))
      (node (ref "J1") (pin "22") (pinfunction "22_22") (pintype "passive"))
      (node (ref "J1") (pin "23") (pinfunction "23_23") (pintype "passive"))
      (node (ref "J1") (pin "24") (pinfunction "24_24") (pintype "passive"))
      (node (ref "J1") (pin "25") (pinfunction "25_25") (pintype "passive"))
      (node (ref "J16") (pin "2") (pinfunction "2_2") (pintype "passive"))
      (node (ref "J17") (pin "10") (pinfunction "10_10") (pintype "passive"))
      (node (ref "J2") (pin "18") (pinfunction "18_18") (pintype "passive"))
      (node (ref "J2") (pin "19") (pinfunction "19_19") (pintype "passive"))
      (node (ref "J2") (pin "20") (pinfunction "20_20") (pintype "passive"))
      (node (ref "J2") (pin "21") (pinfunction "21_21") (pintype "passive"))
      (node (ref "J2") (pin "22") (pinfunction "22_22") (pintype "passive"))
      (node (ref "J2") (pin "23") (pinfunction "23_23") (pintype "passive"))
      (node (ref "J2") (pin "24") (pinfunction "24_24") (pintype "passive"))
      (node (ref "J2") (pin "25") (pinfunction "25_25") (pintype "passive"))
      (node (ref "J3") (pin "18") (pinfunction "18_18") (pintype "passive"))
      (node (ref "J3") (pin "19") (pinfunction "19_19") (pintype "passive"))
      (node (ref "J3") (pin "20") (pinfunction "20_20") (pintype "passive"))
      (node (ref "J3") (pin "21") (pinfunction "21_21") (pintype "passive"))
      (node (ref "J3") (pin "22") (pinfunction "22_22") (pintype "passive"))
      (node (ref "J3") (pin "23") (pinfunction "23_23") (pintype "passive"))
      (node (ref "J3") (pin "24") (pinfunction "24_24") (pintype "passive"))
      (node (ref "J3") (pin "25") (pinfunction "25_25") (pintype "passive"))
      (node (ref "J4") (pin "11") (pinfunction "11_11") (pintype "passive"))
      (node (ref "J4") (pin "2") (pinfunction "2_2") (pintype "passive"))
      (node (ref "J4") (pin "7") (pinfunction "7_7") (pintype "passive"))
      (node (ref "J4") (pin "9") (pinfunction "9_9") (pintype "passive"))
      (node (ref "J5") (pin "11") (pinfunction "11_11") (pintype "passive"))
      (node (ref "J5") (pin "2") (pinfunction "2_2") (pintype "passive"))
      (node (ref "J5") (pin "7") (pinfunction "7_7") (pintype "passive"))
      (node (ref "J5") (pin "9") (pinfunction "9_9") (pintype "passive"))
      (node (ref "J6") (pin "11") (pinfunction "11_11") (pintype "passive"))
      (node (ref "J6") (pin "2") (pinfunction "2_2") (pintype "passive"))
      (node (ref "J6") (pin "7") (pinfunction "7_7") (pintype "passive"))
      (node (ref "J6") (pin "9") (pinfunction "9_9") (pintype "passive"))
      (node (ref "J7") (pin "2") (pinfunction "2_2") (pintype "passive"))
      (node (ref "R10") (pin "1") (pinfunction "1_1") (pintype "passive"))
      (node (ref "R4") (pin "1") (pinfunction "1_1") (pintype "passive"))
      (node (ref "R5") (pin "1") (pinfunction "1_1") (pintype "passive"))
      (node (ref "R6") (pin "1") (pinfunction "1_1") (pintype "passive"))
      (node (ref "R7") (pin "1") (pinfunction "1_1") (pintype "passive"))
      (node (ref "R8") (pin "1") (pinfunction "1_1") (pintype "passive"))
      (node (ref "R9") (pin "1") (pinfunction "1_1") (pintype "passive"))
      (node (ref "TP45") (pin "1") (pinfunction "TP_1") (pintype "passive"))
      (node (ref "TP46") (pin "1") (pinfunction "TP_1") (pintype "passive"))
      (node (ref "TP47") (pin "1") (pinfunction "TP_1") (pintype "passive"))
      (node (ref "U1") (pin "8") (pinfunction "GND_8") (pintype "passive"))
      (node (ref "U2") (pin "8") (pinfunction "GND_8") (pintype "passive"))
      (node (ref "U3") (pin "8") (pinfunction "GND_8") (pintype "passive"))
    )
    (net (code "76") (name "Net-(D1-ANODE)") (class "Default")
      (node (ref "D1") (pin "A") (pinfunction "ANODE_A") (pintype "passive"))
      (node (ref "R2") (pin "1") (pinfunction "1_1") (pintype "passive"))
    )
    (net (code "77") (name "Net-(D2-ANODE)") (class "Default")
      (node (ref "D2") (pin "A") (pinfunction "ANODE_A") (pintype "passive"))
      (node (ref "R3") (pin "1") (pinfunction "1_1") (pintype "passive"))
    )
    (net (code "78") (name "Net-(J4-GND-PadZ1)") (class "Default")
      (node (ref "J4") (pin "Z1") (pinfunction "GND_Z1") (pintype "passive"))
      (node (ref "J4") (pin "Z2") (pinfunction "GND_Z2") (pintype "passive"))
      (node (ref "JP7") (pin "2") (pinfunction "2_2") (pintype "passive"))
    )
    (net (code "79") (name "Net-(J4-Pad6)") (class "Default")
      (node (ref "J4") (pin "6") (pinfunction "6_6") (pintype "passive"))
      (node (ref "R11") (pin "2") (pinfunction "2_2") (pintype "passive"))
    )
    (net (code "80") (name "Net-(J4-Pad8)") (class "Default")
      (node (ref "J4") (pin "8") (pinfunction "8_8") (pintype "passive"))
      (node (ref "R12") (pin "2") (pinfunction "2_2") (pintype "passive"))
    )
    (net (code "81") (name "Net-(J5-GND-PadZ1)") (class "Default")
      (node (ref "J5") (pin "Z1") (pinfunction "GND_Z1") (pintype "passive"))
      (node (ref "J5") (pin "Z2") (pinfunction "GND_Z2") (pintype "passive"))
      (node (ref "JP8") (pin "2") (pinfunction "2_2") (pintype "passive"))
    )
    (net (code "82") (name "Net-(J5-Pad6)") (class "Default")
      (node (ref "J5") (pin "6") (pinfunction "6_6") (pintype "passive"))
      (node (ref "R13") (pin "2") (pinfunction "2_2") (pintype "passive"))
    )
    (net (code "83") (name "Net-(J5-Pad8)") (class "Default")
      (node (ref "J5") (pin "8") (pinfunction "8_8") (pintype "passive"))
      (node (ref "R14") (pin "2") (pinfunction "2_2") (pintype "passive"))
    )
    (net (code "84") (name "Net-(J6-GND-PadZ1)") (class "Default")
      (node (ref "J6") (pin "Z1") (pinfunction "GND_Z1") (pintype "passive"))
      (node (ref "J6") (pin "Z2") (pinfunction "GND_Z2") (pintype "passive"))
      (node (ref "JP9") (pin "2") (pinfunction "2_2") (pintype "passive"))
    )
    (net (code "85") (name "Net-(J6-Pad6)") (class "Default")
      (node (ref "J6") (pin "6") (pinfunction "6_6") (pintype "passive"))
      (node (ref "R15") (pin "2") (pinfunction "2_2") (pintype "passive"))
    )
    (net (code "86") (name "Net-(J6-Pad8)") (class "Default")
      (node (ref "J6") (pin "8") (pinfunction "8_8") (pintype "passive"))
      (node (ref "R16") (pin "2") (pinfunction "2_2") (pintype "passive"))
    )
    (net (code "87") (name "Net-(J18-GND-PadZ1)") (class "Default")
      (node (ref "J18") (pin "9") (pinfunction "9_9") (pintype "passive"))
      (node (ref "J18") (pin "Z1") (pinfunction "GND_Z1") (pintype "passive"))
      (node (ref "J18") (pin "Z2") (pinfunction "GND_Z2") (pintype "passive"))
      (node (ref "JP10") (pin "1") (pinfunction "1_1") (pintype "passive"))
    )
    (net (code "88") (name "Net-(J18-Pad8)") (class "Default")
      (node (ref "J18") (pin "8") (pinfunction "8_8") (pintype "passive"))
      (node (ref "R1") (pin "1") (pinfunction "1_1") (pintype "passive"))
    )
    (net (code "89") (name "Net-(TP6-TP)") (class "Default")
      (node (ref "J1") (pin "14") (pinfunction "14_14") (pintype "passive"))
      (node (ref "TP6") (pin "1") (pinfunction "TP_1") (pintype "passive"))
    )
    (net (code "90") (name "Net-(TP7-TP)") (class "Default")
      (node (ref "J1") (pin "15") (pinfunction "15_15") (pintype "passive"))
      (node (ref "TP7") (pin "1") (pinfunction "TP_1") (pintype "passive"))
    )
    (net (code "91") (name "Net-(TP8-TP)") (class "Default")
      (node (ref "J1") (pin "16") (pinfunction "16_16") (pintype "passive"))
      (node (ref "TP8") (pin "1") (pinfunction "TP_1") (pintype "passive"))
    )
    (net (code "92") (name "Net-(TP9-TP)") (class "Default")
      (node (ref "J1") (pin "17") (pinfunction "17_17") (pintype "passive"))
      (node (ref "TP9") (pin "1") (pinfunction "TP_1") (pintype "passive"))
    )
    (net (code "93") (name "Net-(TP10-TP)") (class "Default")
      (node (ref "J1") (pin "10") (pinfunction "10_10") (pintype "passive"))
      (node (ref "TP10") (pin "1") (pinfunction "TP_1") (pintype "passive"))
    )
    (net (code "94") (name "Net-(TP11-TP)") (class "Default")
      (node (ref "J1") (pin "11") (pinfunction "11_11") (pintype "passive"))
      (node (ref "TP11") (pin "1") (pinfunction "TP_1") (pintype "passive"))
    )
    (net (code "95") (name "Net-(TP12-TP)") (class "Default")
      (node (ref "J1") (pin "12") (pinfunction "12_12") (pintype "passive"))
      (node (ref "TP12") (pin "1") (pinfunction "TP_1") (pintype "passive"))
    )
    (net (code "96") (name "Net-(TP13-TP)") (class "Default")
      (node (ref "J1") (pin "13") (pinfunction "13_13") (pintype "passive"))
      (node (ref "TP13") (pin "1") (pinfunction "TP_1") (pintype "passive"))
    )
    (net (code "97") (name "Net-(TP17-TP)") (class "Default")
      (node (ref "J2") (pin "15") (pinfunction "15_15") (pintype "passive"))
      (node (ref "TP17") (pin "1") (pinfunction "TP_1") (pintype "passive"))
    )
    (net (code "98") (name "Net-(TP20-TP)") (class "Default")
      (node (ref "J2") (pin "8") (pinfunction "8_8") (pintype "passive"))
      (node (ref "TP20") (pin "1") (pinfunction "TP_1") (pintype "passive"))
    )
    (net (code "99") (name "Net-(TP21-TP)") (class "Default")
      (node (ref "J2") (pin "9") (pinfunction "9_9") (pintype "passive"))
      (node (ref "TP21") (pin "1") (pinfunction "TP_1") (pintype "passive"))
    )
    (net (code "100") (name "Net-(TP22-TP)") (class "Default")
      (node (ref "J2") (pin "10") (pinfunction "10_10") (pintype "passive"))
      (node (ref "TP22") (pin "1") (pinfunction "TP_1") (pintype "passive"))
    )
    (net (code "101") (name "Net-(TP23-TP)") (class "Default")
      (node (ref "J2") (pin "11") (pinfunction "11_11") (pintype "passive"))
      (node (ref "TP23") (pin "1") (pinfunction "TP_1") (pintype "passive"))
    )
    (net (code "102") (name "Net-(TP24-TP)") (class "Default")
      (node (ref "J2") (pin "12") (pinfunction "12_12") (pintype "passive"))
      (node (ref "TP24") (pin "1") (pinfunction "TP_1") (pintype "passive"))
    )
    (net (code "103") (name "Net-(TP25-TP)") (class "Default")
      (node (ref "J2") (pin "13") (pinfunction "13_13") (pintype "passive"))
      (node (ref "TP25") (pin "1") (pinfunction "TP_1") (pintype "passive"))
    )
    (net (code "104") (name "Net-(TP26-TP)") (class "Default")
      (node (ref "J3") (pin "15") (pinfunction "15_15") (pintype "passive"))
      (node (ref "TP26") (pin "1") (pinfunction "TP_1") (pintype "passive"))
    )
    (net (code "105") (name "Net-(TP27-TP)") (class "Default")
      (node (ref "TP27") (pin "1") (pinfunction "TP_1") (pintype "passive"))
      (node (ref "U3") (pin "4") (pinfunction "IN4_4") (pintype "passive"))
    )
    (net (code "106") (name "Net-(TP28-TP)") (class "Default")
      (node (ref "TP28") (pin "1") (pinfunction "TP_1") (pintype "passive"))
      (node (ref "U3") (pin "13") (pinfunction "OUT4_13") (pintype "passive"))
    )
    (net (code "107") (name "Net-(TP30-TP)") (class "Default")
      (node (ref "TP30") (pin "1") (pinfunction "TP_1") (pintype "passive"))
      (node (ref "U3") (pin "5") (pinfunction "IN5_5") (pintype "passive"))
    )
    (net (code "108") (name "Net-(TP31-TP)") (class "Default")
      (node (ref "TP31") (pin "1") (pinfunction "TP_1") (pintype "passive"))
      (node (ref "U3") (pin "12") (pinfunction "OUT5_12") (pintype "passive"))
    )
    (net (code "109") (name "Net-(TP32-TP)") (class "Default")
      (node (ref "TP32") (pin "1") (pinfunction "TP_1") (pintype "passive"))
      (node (ref "U3") (pin "6") (pinfunction "IN6_6") (pintype "passive"))
    )
    (net (code "110") (name "Net-(TP33-TP)") (class "Default")
      (node (ref "TP33") (pin "1") (pinfunction "TP_1") (pintype "passive"))
      (node (ref "U3") (pin "11") (pinfunction "OUT6_11") (pintype "passive"))
    )
    (net (code "111") (name "Net-(TP35-TP)") (class "Default")
      (node (ref "TP35") (pin "1") (pinfunction "TP_1") (pintype "passive"))
      (node (ref "U3") (pin "7") (pinfunction "IN7_7") (pintype "passive"))
    )
    (net (code "112") (name "Net-(TP36-TP)") (class "Default")
      (node (ref "TP36") (pin "1") (pinfunction "TP_1") (pintype "passive"))
      (node (ref "U3") (pin "10") (pinfunction "OUT7_10") (pintype "passive"))
    )
    (net (code "113") (name "Net-(TP38-TP)") (class "Default")
      (node (ref "J3") (pin "10") (pinfunction "10_10") (pintype "passive"))
      (node (ref "TP38") (pin "1") (pinfunction "TP_1") (pintype "passive"))
    )
    (net (code "114") (name "Net-(TP39-TP)") (class "Default")
      (node (ref "J3") (pin "11") (pinfunction "11_11") (pintype "passive"))
      (node (ref "TP39") (pin "1") (pinfunction "TP_1") (pintype "passive"))
    )
    (net (code "115") (name "Net-(TP41-TP)") (class "Default")
      (node (ref "J3") (pin "12") (pinfunction "12_12") (pintype "passive"))
      (node (ref "TP41") (pin "1") (pinfunction "TP_1") (pintype "passive"))
    )
    (net (code "116") (name "Net-(TP42-TP)") (class "Default")
      (node (ref "J3") (pin "13") (pinfunction "13_13") (pintype "passive"))
      (node (ref "TP42") (pin "1") (pinfunction "TP_1") (pintype "passive"))
    )
    (net (code "117") (name "unconnected-(J18-Pad7)") (class "Default")
      (node (ref "J18") (pin "7") (pinfunction "7_7") (pintype "passive"))
    )
    (net (code "118") (name "unconnected-(K1-Pad8)") (class "Default")
      (node (ref "K1") (pin "8") (pinfunction "8_8") (pintype "passive"))
    )
    (net (code "119") (name "unconnected-(K1-Pad9)") (class "Default")
      (node (ref "K1") (pin "9") (pinfunction "9_9") (pintype "passive"))
    )
    (net (code "120") (name "unconnected-(K1-Pad10)") (class "Default")
      (node (ref "K1") (pin "10") (pinfunction "10_10") (pintype "passive"))
    )
  )
)
